# APM32F103C8T6.net
KiCad netlist of a schematic drawn in Altium Designer
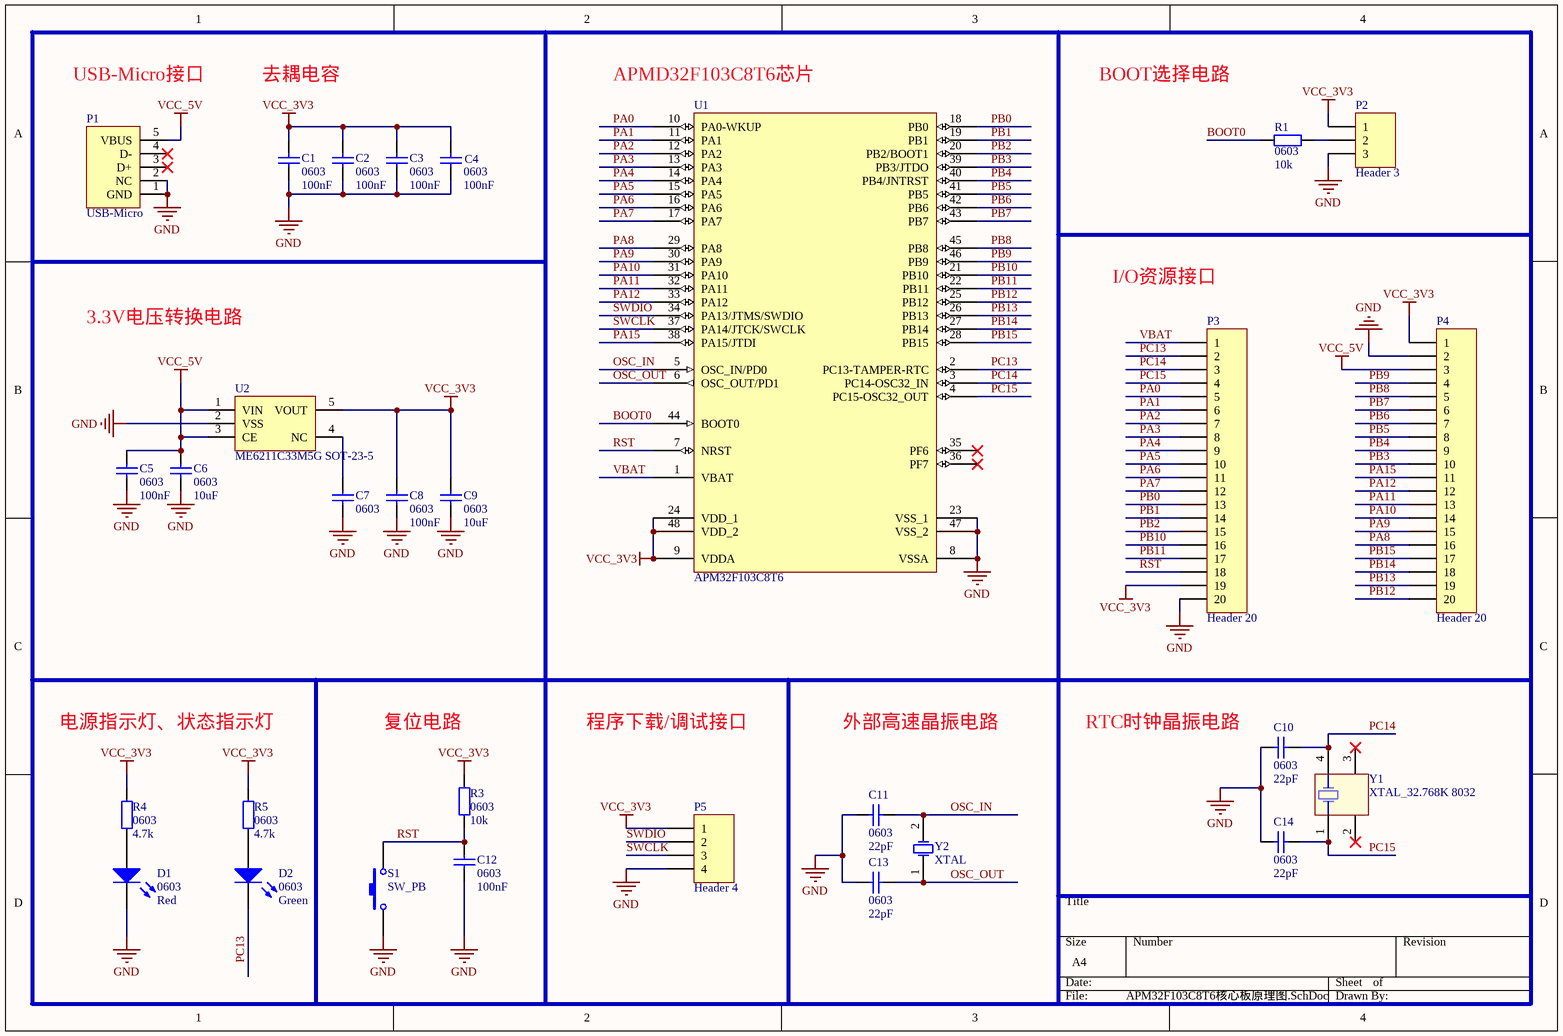
[diagram p0: APM32F103C8T6核心板原理图.SchDoc]

(export (version "E")
  (design (tool "Eeschema 10.0.6"))
  (components
    (comp (ref "C1")
      (value "100nF")
      (footprint "0603")
      (description "Capacitor 0603")
      (fields (field (name "Comment") "Cap 0603"))
      (libsource (lib "Schlib1") (part "Cap 0603"))
    )
    (comp (ref "C2")
      (value "100nF")
      (footprint "0603")
      (description "Capacitor 0603")
      (fields (field (name "Comment") "Cap 0603"))
      (libsource (lib "Schlib1") (part "Cap 0603"))
    )
    (comp (ref "C3")
      (value "100nF")
      (footprint "0603")
      (description "Capacitor 0603")
      (fields (field (name "Comment") "Cap 0603"))
      (libsource (lib "Schlib1") (part "Cap 0603"))
    )
    (comp (ref "C4")
      (value "100nF")
      (footprint "0603")
      (description "Capacitor 0603")
      (fields (field (name "Comment") "Cap 0603"))
      (libsource (lib "Schlib1") (part "Cap 0603"))
    )
    (comp (ref "C5")
      (value "100nF")
      (footprint "0603")
      (description "Capacitor 0603")
      (fields (field (name "Comment") "Cap 0603"))
      (libsource (lib "Schlib1") (part "Cap 0603"))
    )
    (comp (ref "C6")
      (value "10uF")
      (footprint "0603")
      (description "Capacitor 0603")
      (fields (field (name "Comment") "Cap 0603"))
      (libsource (lib "Schlib1") (part "Cap 0603"))
    )
    (comp (ref "C7")
      (value "Cap 0603")
      (footprint "0603")
      (description "Capacitor 0603")
      (libsource (lib "Schlib1") (part "Cap 0603"))
    )
    (comp (ref "C8")
      (value "100nF")
      (footprint "0603")
      (description "Capacitor 0603")
      (fields (field (name "Comment") "Cap 0603"))
      (libsource (lib "Schlib1") (part "Cap 0603"))
    )
    (comp (ref "C9")
      (value "10uF")
      (footprint "0603")
      (description "Capacitor 0603")
      (fields (field (name "Comment") "Cap 0603"))
      (libsource (lib "Schlib1") (part "Cap 0603"))
    )
    (comp (ref "C10")
      (value "22pF")
      (footprint "0603")
      (description "Capacitor 0603")
      (fields (field (name "Comment") "Cap 0603"))
      (libsource (lib "Schlib1") (part "Cap 0603"))
    )
    (comp (ref "C11")
      (value "22pF")
      (footprint "0603")
      (description "Capacitor 0603")
      (fields (field (name "Comment") "Cap 0603"))
      (libsource (lib "Schlib1") (part "Cap 0603"))
    )
    (comp (ref "C12")
      (value "100nF")
      (footprint "0603")
      (description "Capacitor 0603")
      (fields (field (name "Comment") "Cap 0603"))
      (libsource (lib "Schlib1") (part "Cap 0603"))
    )
    (comp (ref "C13")
      (value "22pF")
      (footprint "0603")
      (description "Capacitor 0603")
      (fields (field (name "Comment") "Cap 0603"))
      (libsource (lib "Schlib1") (part "Cap 0603"))
    )
    (comp (ref "C14")
      (value "22pF")
      (footprint "0603")
      (description "Capacitor 0603")
      (fields (field (name "Comment") "Cap 0603"))
      (libsource (lib "Schlib1") (part "Cap 0603"))
    )
    (comp (ref "D1")
      (value "Red")
      (footprint "0603")
      (description "LED 0603")
      (libsource (lib "Schlib1") (part "LED 0603"))
    )
    (comp (ref "D2")
      (value "Green")
      (footprint "0603")
      (description "LED 0603")
      (libsource (lib "Schlib1") (part "LED 0603"))
    )
    (comp (ref "P1")
      (value "USB-Micro")
      (footprint "USB Micro")
      (libsource (lib "Schlib1") (part "USB-Micro"))
    )
    (comp (ref "P2")
      (value "Header 3")
      (footprint "HDR1X3")
      (description "Header, 3-Pin")
      (fields (field (name "PUBLISHER") "Altium Limited"))
      (libsource (lib "Miscellaneous Connectors") (part "Header 3"))
    )
    (comp (ref "P3")
      (value "Header 20")
      (footprint "HDR1X20")
      (description "Header, 20-Pin")
      (fields (field (name "PUBLISHER") "Altium Limited"))
      (libsource (lib "Miscellaneous Connectors") (part "Header 20"))
    )
    (comp (ref "P4")
      (value "Header 20")
      (footprint "HDR1X20")
      (description "Header, 20-Pin")
      (fields (field (name "PUBLISHER") "Altium Limited"))
      (libsource (lib "Miscellaneous Connectors") (part "Header 20"))
    )
    (comp (ref "P5")
      (value "Header 4")
      (footprint "HDR1X4")
      (description "Header, 4-Pin")
      (fields (field (name "PUBLISHER") "Altium Limited"))
      (libsource (lib "Miscellaneous Connectors") (part "Header 4"))
    )
    (comp (ref "R1")
      (value "10k")
      (footprint "0603")
      (description "Resistor 0603")
      (fields (field (name "Comment") "Res 0603"))
      (libsource (lib "") (part "Res 0603_2"))
    )
    (comp (ref "R3")
      (value "10k")
      (footprint "0603")
      (description "Resistor 0603")
      (fields (field (name "Comment") "Res 0603"))
      (libsource (lib "Schlib1") (part "Res 0603"))
    )
    (comp (ref "R4")
      (value "4.7k")
      (footprint "0603")
      (description "Resistor 0603")
      (fields (field (name "Comment") "Res 0603"))
      (libsource (lib "") (part "Res 0603_1"))
    )
    (comp (ref "R5")
      (value "4.7k")
      (footprint "0603")
      (description "Resistor 0603")
      (fields (field (name "Comment") "Res 0603"))
      (libsource (lib "") (part "Res 0603_1"))
    )
    (comp (ref "S1") (value "SW_PB") (footprint "SW-2Pin") (libsource (lib "Schlib1") (part "SW_PB")))
    (comp (ref "U1")
      (value "APM32F103C8T6")
      (footprint "TQFP48_M")
      (description "STM32F030C8T6 LQFP48")
      (libsource (lib "STM32F103C8T6核心板原理图") (part "STM32F030C8T6"))
    )
    (comp (ref "U2")
      (value "ME6211C33M5G SOT-23-5")
      (footprint "SOT-23-5")
      (libsource (lib "Schlib1") (part "ME6211C33M5G"))
    )
    (comp (ref "Y1")
      (value "XTAL_32.768K 8032")
      (footprint "XTAL_8032")
      (libsource (lib "Schlib1") (part "XTAL_32.768K 8032"))
    )
    (comp (ref "Y2")
      (value "XTAL")
      (footprint "XTAL_49S")
      (description "XTAL 8MHZ")
      (libsource (lib "Schlib1") (part "XTAL 8MHZ"))
    )
  )
  (nets
    (net (code "1") (name "/BOOT0") (class "Default")
      (node (ref "R1") (pin "1") (pinfunction "1_1") (pintype "passive"))
      (node (ref "U1") (pin "44") (pinfunction "BOOT0_44") (pintype "input"))
    )
    (net (code "2") (name "/OSC_IN") (class "Default")
      (node (ref "C11") (pin "1") (pinfunction "1_1") (pintype "passive"))
      (node (ref "U1") (pin "5") (pinfunction "OSC_IN/PD0_5") (pintype "input"))
      (node (ref "Y2") (pin "2") (pinfunction "OSC2_2") (pintype "passive"))
    )
    (net (code "3") (name "/OSC_OUT") (class "Default")
      (node (ref "C13") (pin "1") (pinfunction "1_1") (pintype "passive"))
      (node (ref "U1") (pin "6") (pinfunction "OSC_OUT/PD1_6") (pintype "output"))
      (node (ref "Y2") (pin "1") (pinfunction "OSC1_1") (pintype "passive"))
    )
    (net (code "4") (name "/PA0") (class "Default")
      (node (ref "P3") (pin "5") (pinfunction "5_5") (pintype "passive"))
      (node (ref "U1") (pin "10") (pinfunction "PA0-WKUP_10") (pintype "bidirectional"))
    )
    (net (code "5") (name "/PA1") (class "Default")
      (node (ref "P3") (pin "6") (pinfunction "6_6") (pintype "passive"))
      (node (ref "U1") (pin "11") (pinfunction "PA1_11") (pintype "bidirectional"))
    )
    (net (code "6") (name "/PA2") (class "Default")
      (node (ref "P3") (pin "7") (pinfunction "7_7") (pintype "passive"))
      (node (ref "U1") (pin "12") (pinfunction "PA2_12") (pintype "bidirectional"))
    )
    (net (code "7") (name "/PA3") (class "Default")
      (node (ref "P3") (pin "8") (pinfunction "8_8") (pintype "passive"))
      (node (ref "U1") (pin "13") (pinfunction "PA3_13") (pintype "bidirectional"))
    )
    (net (code "8") (name "/PA4") (class "Default")
      (node (ref "P3") (pin "9") (pinfunction "9_9") (pintype "passive"))
      (node (ref "U1") (pin "14") (pinfunction "PA4_14") (pintype "bidirectional"))
    )
    (net (code "9") (name "/PA5") (class "Default")
      (node (ref "P3") (pin "10") (pinfunction "10_10") (pintype "passive"))
      (node (ref "U1") (pin "15") (pinfunction "PA5_15") (pintype "bidirectional"))
    )
    (net (code "10") (name "/PA6") (class "Default")
      (node (ref "P3") (pin "11") (pinfunction "11_11") (pintype "passive"))
      (node (ref "U1") (pin "16") (pinfunction "PA6_16") (pintype "bidirectional"))
    )
    (net (code "11") (name "/PA7") (class "Default")
      (node (ref "P3") (pin "12") (pinfunction "12_12") (pintype "passive"))
      (node (ref "U1") (pin "17") (pinfunction "PA7_17") (pintype "bidirectional"))
    )
    (net (code "12") (name "/PA8") (class "Default")
      (node (ref "P4") (pin "16") (pinfunction "16_16") (pintype "passive"))
      (node (ref "U1") (pin "29") (pinfunction "PA8_29") (pintype "bidirectional"))
    )
    (net (code "13") (name "/PA9") (class "Default")
      (node (ref "P4") (pin "15") (pinfunction "15_15") (pintype "passive"))
      (node (ref "U1") (pin "30") (pinfunction "PA9_30") (pintype "bidirectional"))
    )
    (net (code "14") (name "/PA10") (class "Default")
      (node (ref "P4") (pin "14") (pinfunction "14_14") (pintype "passive"))
      (node (ref "U1") (pin "31") (pinfunction "PA10_31") (pintype "bidirectional"))
    )
    (net (code "15") (name "/PA11") (class "Default")
      (node (ref "P4") (pin "13") (pinfunction "13_13") (pintype "passive"))
      (node (ref "U1") (pin "32") (pinfunction "PA11_32") (pintype "bidirectional"))
    )
    (net (code "16") (name "/PA12") (class "Default")
      (node (ref "P4") (pin "12") (pinfunction "12_12") (pintype "passive"))
      (node (ref "U1") (pin "33") (pinfunction "PA12_33") (pintype "bidirectional"))
    )
    (net (code "17") (name "/PA15") (class "Default")
      (node (ref "P4") (pin "11") (pinfunction "11_11") (pintype "passive"))
      (node (ref "U1") (pin "38") (pinfunction "PA15/JTDI_38") (pintype "bidirectional"))
    )
    (net (code "18") (name "/PB0") (class "Default")
      (node (ref "P3") (pin "13") (pinfunction "13_13") (pintype "passive"))
      (node (ref "U1") (pin "18") (pinfunction "PB0_18") (pintype "bidirectional"))
    )
    (net (code "19") (name "/PB1") (class "Default")
      (node (ref "P3") (pin "14") (pinfunction "14_14") (pintype "passive"))
      (node (ref "U1") (pin "19") (pinfunction "PB1_19") (pintype "bidirectional"))
    )
    (net (code "20") (name "/PB2") (class "Default")
      (node (ref "P3") (pin "15") (pinfunction "15_15") (pintype "passive"))
      (node (ref "U1") (pin "20") (pinfunction "PB2/BOOT1_20") (pintype "bidirectional"))
    )
    (net (code "21") (name "/PB3") (class "Default")
      (node (ref "P4") (pin "10") (pinfunction "10_10") (pintype "passive"))
      (node (ref "U1") (pin "39") (pinfunction "PB3/JTDO_39") (pintype "bidirectional"))
    )
    (net (code "22") (name "/PB4") (class "Default")
      (node (ref "P4") (pin "9") (pinfunction "9_9") (pintype "passive"))
      (node (ref "U1") (pin "40") (pinfunction "PB4/JNTRST_40") (pintype "bidirectional"))
    )
    (net (code "23") (name "/PB5") (class "Default")
      (node (ref "P4") (pin "8") (pinfunction "8_8") (pintype "passive"))
      (node (ref "U1") (pin "41") (pinfunction "PB5_41") (pintype "bidirectional"))
    )
    (net (code "24") (name "/PB6") (class "Default")
      (node (ref "P4") (pin "7") (pinfunction "7_7") (pintype "passive"))
      (node (ref "U1") (pin "42") (pinfunction "PB6_42") (pintype "bidirectional"))
    )
    (net (code "25") (name "/PB7") (class "Default")
      (node (ref "P4") (pin "6") (pinfunction "6_6") (pintype "passive"))
      (node (ref "U1") (pin "43") (pinfunction "PB7_43") (pintype "bidirectional"))
    )
    (net (code "26") (name "/PB8") (class "Default")
      (node (ref "P4") (pin "5") (pinfunction "5_5") (pintype "passive"))
      (node (ref "U1") (pin "45") (pinfunction "PB8_45") (pintype "bidirectional"))
    )
    (net (code "27") (name "/PB9") (class "Default")
      (node (ref "P4") (pin "4") (pinfunction "4_4") (pintype "passive"))
      (node (ref "U1") (pin "46") (pinfunction "PB9_46") (pintype "bidirectional"))
    )
    (net (code "28") (name "/PB10") (class "Default")
      (node (ref "P3") (pin "16") (pinfunction "16_16") (pintype "passive"))
      (node (ref "U1") (pin "21") (pinfunction "PB10_21") (pintype "bidirectional"))
    )
    (net (code "29") (name "/PB11") (class "Default")
      (node (ref "P3") (pin "17") (pinfunction "17_17") (pintype "passive"))
      (node (ref "U1") (pin "22") (pinfunction "PB11_22") (pintype "bidirectional"))
    )
    (net (code "30") (name "/PB12") (class "Default")
      (node (ref "P4") (pin "20") (pinfunction "20_20") (pintype "passive"))
      (node (ref "U1") (pin "25") (pinfunction "PB12_25") (pintype "bidirectional"))
    )
    (net (code "31") (name "/PB13") (class "Default")
      (node (ref "P4") (pin "19") (pinfunction "19_19") (pintype "passive"))
      (node (ref "U1") (pin "26") (pinfunction "PB13_26") (pintype "bidirectional"))
    )
    (net (code "32") (name "/PB14") (class "Default")
      (node (ref "P4") (pin "18") (pinfunction "18_18") (pintype "passive"))
      (node (ref "U1") (pin "27") (pinfunction "PB14_27") (pintype "bidirectional"))
    )
    (net (code "33") (name "/PB15") (class "Default")
      (node (ref "P4") (pin "17") (pinfunction "17_17") (pintype "passive"))
      (node (ref "U1") (pin "28") (pinfunction "PB15_28") (pintype "bidirectional"))
    )
    (net (code "34") (name "/PC13") (class "Default")
      (node (ref "D2") (pin "2") (pinfunction "K_2") (pintype "passive"))
      (node (ref "P3") (pin "2") (pinfunction "2_2") (pintype "passive"))
      (node (ref "U1") (pin "2") (pinfunction "PC13-TAMPER-RTC_2") (pintype "bidirectional"))
    )
    (net (code "35") (name "/PC14") (class "Default")
      (node (ref "C10") (pin "1") (pinfunction "1_1") (pintype "passive"))
      (node (ref "P3") (pin "3") (pinfunction "3_3") (pintype "passive"))
      (node (ref "U1") (pin "3") (pinfunction "PC14-OSC32_IN_3") (pintype "bidirectional"))
      (node (ref "Y1") (pin "4") (pinfunction "OSC2_4") (pintype "passive"))
    )
    (net (code "36") (name "/PC15") (class "Default")
      (node (ref "C14") (pin "1") (pinfunction "1_1") (pintype "passive"))
      (node (ref "P3") (pin "4") (pinfunction "4_4") (pintype "passive"))
      (node (ref "U1") (pin "4") (pinfunction "PC15-OSC32_OUT_4") (pintype "bidirectional"))
      (node (ref "Y1") (pin "1") (pinfunction "OSC1_1") (pintype "passive"))
    )
    (net (code "37") (name "/RST") (class "Default")
      (node (ref "C12") (pin "2") (pinfunction "2_2") (pintype "passive"))
      (node (ref "P3") (pin "18") (pinfunction "18_18") (pintype "passive"))
      (node (ref "R3") (pin "1") (pinfunction "1_1") (pintype "passive"))
      (node (ref "S1") (pin "2") (pinfunction "2_2") (pintype "passive"))
      (node (ref "U1") (pin "7") (pinfunction "NRST_7") (pintype "bidirectional"))
    )
    (net (code "38") (name "/SWCLK") (class "Default")
      (node (ref "P5") (pin "3") (pinfunction "3_3") (pintype "passive"))
      (node (ref "U1") (pin "37") (pinfunction "PA14/JTCK/SWCLK_37") (pintype "bidirectional"))
    )
    (net (code "39") (name "/SWDIO") (class "Default")
      (node (ref "P5") (pin "2") (pinfunction "2_2") (pintype "passive"))
      (node (ref "U1") (pin "34") (pinfunction "PA13/JTMS/SWDIO_34") (pintype "bidirectional"))
    )
    (net (code "40") (name "/VBAT") (class "Default")
      (node (ref "P3") (pin "1") (pinfunction "1_1") (pintype "passive"))
      (node (ref "U1") (pin "1") (pinfunction "VBAT_1") (pintype "power_in"))
    )
    (net (code "41") (name "GND") (class "Default")
      (node (ref "C1") (pin "1") (pinfunction "1_1") (pintype "passive"))
      (node (ref "C10") (pin "2") (pinfunction "2_2") (pintype "passive"))
      (node (ref "C11") (pin "2") (pinfunction "2_2") (pintype "passive"))
      (node (ref "C12") (pin "1") (pinfunction "1_1") (pintype "passive"))
      (node (ref "C13") (pin "2") (pinfunction "2_2") (pintype "passive"))
      (node (ref "C14") (pin "2") (pinfunction "2_2") (pintype "passive"))
      (node (ref "C2") (pin "1") (pinfunction "1_1") (pintype "passive"))
      (node (ref "C3") (pin "1") (pinfunction "1_1") (pintype "passive"))
      (node (ref "C4") (pin "1") (pinfunction "1_1") (pintype "passive"))
      (node (ref "C5") (pin "1") (pinfunction "1_1") (pintype "passive"))
      (node (ref "C6") (pin "1") (pinfunction "1_1") (pintype "passive"))
      (node (ref "C7") (pin "1") (pinfunction "1_1") (pintype "passive"))
      (node (ref "C8") (pin "1") (pinfunction "1_1") (pintype "passive"))
      (node (ref "C9") (pin "1") (pinfunction "1_1") (pintype "passive"))
      (node (ref "D1") (pin "2") (pinfunction "K_2") (pintype "passive"))
      (node (ref "P1") (pin "1") (pinfunction "GND_1") (pintype "power_in"))
      (node (ref "P1") (pin "2") (pinfunction "NC_2") (pintype "power_in"))
      (node (ref "P2") (pin "3") (pinfunction "3_3") (pintype "passive"))
      (node (ref "P3") (pin "20") (pinfunction "20_20") (pintype "passive"))
      (node (ref "P4") (pin "2") (pinfunction "2_2") (pintype "passive"))
      (node (ref "P5") (pin "4") (pinfunction "4_4") (pintype "passive"))
      (node (ref "S1") (pin "1") (pinfunction "1_1") (pintype "passive"))
      (node (ref "U1") (pin "23") (pinfunction "VSS_1_23") (pintype "power_in"))
      (node (ref "U1") (pin "47") (pinfunction "VSS_2_47") (pintype "power_in"))
      (node (ref "U1") (pin "8") (pinfunction "VSSA_8") (pintype "power_in"))
      (node (ref "U2") (pin "2") (pinfunction "VSS_2") (pintype "power_in"))
    )
    (net (code "42") (name "Net-(D1-A)") (class "Default")
      (node (ref "D1") (pin "1") (pinfunction "A_1") (pintype "passive"))
      (node (ref "R4") (pin "2") (pinfunction "2_2") (pintype "passive"))
    )
    (net (code "43") (name "Net-(D2-A)") (class "Default")
      (node (ref "D2") (pin "1") (pinfunction "A_1") (pintype "passive"))
      (node (ref "R5") (pin "2") (pinfunction "2_2") (pintype "passive"))
    )
    (net (code "44") (name "Net-(P2-Pad2)") (class "Default")
      (node (ref "P2") (pin "2") (pinfunction "2_2") (pintype "passive"))
      (node (ref "R1") (pin "2") (pinfunction "2_2") (pintype "passive"))
    )
    (net (code "45") (name "Net-(U2-NC)") (class "Default")
      (node (ref "C7") (pin "2") (pinfunction "2_2") (pintype "passive"))
      (node (ref "U2") (pin "4") (pinfunction "NC_4") (pintype "power_in"))
    )
    (net (code "46") (name "VCC_3V3") (class "Default")
      (node (ref "C1") (pin "2") (pinfunction "2_2") (pintype "passive"))
      (node (ref "C2") (pin "2") (pinfunction "2_2") (pintype "passive"))
      (node (ref "C3") (pin "2") (pinfunction "2_2") (pintype "passive"))
      (node (ref "C4") (pin "2") (pinfunction "2_2") (pintype "passive"))
      (node (ref "C8") (pin "2") (pinfunction "2_2") (pintype "passive"))
      (node (ref "C9") (pin "2") (pinfunction "2_2") (pintype "passive"))
      (node (ref "P2") (pin "1") (pinfunction "1_1") (pintype "passive"))
      (node (ref "P3") (pin "19") (pinfunction "19_19") (pintype "passive"))
      (node (ref "P4") (pin "1") (pinfunction "1_1") (pintype "passive"))
      (node (ref "P5") (pin "1") (pinfunction "1_1") (pintype "passive"))
      (node (ref "R3") (pin "2") (pinfunction "2_2") (pintype "passive"))
      (node (ref "R4") (pin "1") (pinfunction "1_1") (pintype "passive"))
      (node (ref "R5") (pin "1") (pinfunction "1_1") (pintype "passive"))
      (node (ref "U1") (pin "24") (pinfunction "VDD_1_24") (pintype "power_in"))
      (node (ref "U1") (pin "48") (pinfunction "VDD_2_48") (pintype "power_in"))
      (node (ref "U1") (pin "9") (pinfunction "VDDA_9") (pintype "power_in"))
      (node (ref "U2") (pin "5") (pinfunction "VOUT_5") (pintype "power_in"))
    )
    (net (code "47") (name "VCC_5V") (class "Default")
      (node (ref "C5") (pin "2") (pinfunction "2_2") (pintype "passive"))
      (node (ref "C6") (pin "2") (pinfunction "2_2") (pintype "passive"))
      (node (ref "P1") (pin "5") (pinfunction "VBUS_5") (pintype "power_in"))
      (node (ref "P4") (pin "3") (pinfunction "3_3") (pintype "passive"))
      (node (ref "U2") (pin "1") (pinfunction "VIN_1") (pintype "power_in"))
      (node (ref "U2") (pin "3") (pinfunction "CE_3") (pintype "power_in"))
    )
    (net (code "48") (name "unconnected-(P1-D+-Pad3)") (class "Default")
      (node (ref "P1") (pin "3") (pinfunction "D+_3") (pintype "power_in+no_connect"))
    )
    (net (code "49") (name "unconnected-(P1-D--Pad4)") (class "Default")
      (node (ref "P1") (pin "4") (pinfunction "D-_4") (pintype "power_in+no_connect"))
    )
    (net (code "50") (name "unconnected-(U1-PF6-Pad35)") (class "Default")
      (node (ref "U1") (pin "35") (pinfunction "PF6_35") (pintype "bidirectional+no_connect"))
    )
    (net (code "51") (name "unconnected-(U1-PF7-Pad36)") (class "Default")
      (node (ref "U1") (pin "36") (pinfunction "PF7_36") (pintype "bidirectional+no_connect"))
    )
    (net (code "52") (name "unconnected-(Y1-NC-Pad2)") (class "Default")
      (node (ref "Y1") (pin "2") (pinfunction "NC_2") (pintype "power_in+no_connect"))
    )
    (net (code "53") (name "unconnected-(Y1-NC-Pad3)") (class "Default")
      (node (ref "Y1") (pin "3") (pinfunction "NC_3") (pintype "power_in+no_connect"))
    )
  )
)
